# RGB_ADDR_THRU.net
KiCad netlist of a schematic drawn in EAGLE
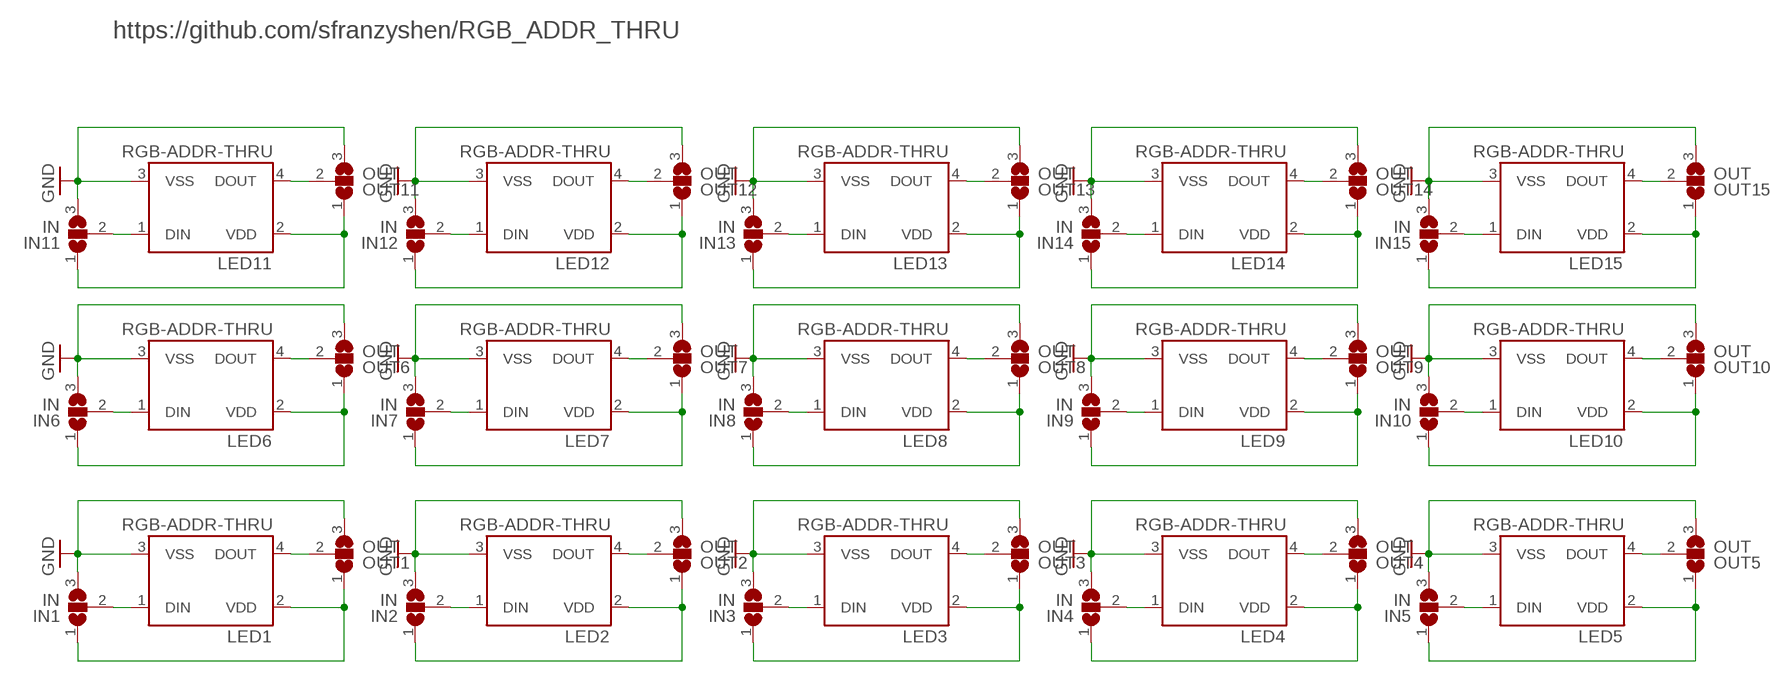
[diagram p0: schematic, sheet 1]

(export (version "E")
  (design (tool "Eeschema 10.0.6"))
  (components
    (comp (ref "IN1")
      (value "IN")
      (footprint "eagle-import:SJ_2W")
      (libsource (lib "eagle-import") (part "SJ2WW"))
    )
    (comp (ref "IN2")
      (value "IN")
      (footprint "eagle-import:SJ_2W")
      (libsource (lib "eagle-import") (part "SJ2WW"))
    )
    (comp (ref "IN3")
      (value "IN")
      (footprint "eagle-import:SJ_2W")
      (libsource (lib "eagle-import") (part "SJ2WW"))
    )
    (comp (ref "IN4")
      (value "IN")
      (footprint "eagle-import:SJ_2W")
      (libsource (lib "eagle-import") (part "SJ2WW"))
    )
    (comp (ref "IN5")
      (value "IN")
      (footprint "eagle-import:SJ_2W")
      (libsource (lib "eagle-import") (part "SJ2WW"))
    )
    (comp (ref "IN6")
      (value "IN")
      (footprint "eagle-import:SJ_2W")
      (libsource (lib "eagle-import") (part "SJ2WW"))
    )
    (comp (ref "IN7")
      (value "IN")
      (footprint "eagle-import:SJ_2W")
      (libsource (lib "eagle-import") (part "SJ2WW"))
    )
    (comp (ref "IN8")
      (value "IN")
      (footprint "eagle-import:SJ_2W")
      (libsource (lib "eagle-import") (part "SJ2WW"))
    )
    (comp (ref "IN9")
      (value "IN")
      (footprint "eagle-import:SJ_2W")
      (libsource (lib "eagle-import") (part "SJ2WW"))
    )
    (comp (ref "IN10")
      (value "IN")
      (footprint "eagle-import:SJ_2W")
      (libsource (lib "eagle-import") (part "SJ2WW"))
    )
    (comp (ref "IN11")
      (value "IN")
      (footprint "eagle-import:SJ_2W")
      (libsource (lib "eagle-import") (part "SJ2WW"))
    )
    (comp (ref "IN12")
      (value "IN")
      (footprint "eagle-import:SJ_2W")
      (libsource (lib "eagle-import") (part "SJ2WW"))
    )
    (comp (ref "IN13")
      (value "IN")
      (footprint "eagle-import:SJ_2W")
      (libsource (lib "eagle-import") (part "SJ2WW"))
    )
    (comp (ref "IN14")
      (value "IN")
      (footprint "eagle-import:SJ_2W")
      (libsource (lib "eagle-import") (part "SJ2WW"))
    )
    (comp (ref "IN15")
      (value "IN")
      (footprint "eagle-import:SJ_2W")
      (libsource (lib "eagle-import") (part "SJ2WW"))
    )
    (comp (ref "LED1")
      (value "RGB-ADDR-THRU")
      (footprint "eagle-import:LED-RGB-THRU")
      (libsource (lib "eagle-import") (part "LED-RGB-ADDR-THRU5MM"))
    )
    (comp (ref "LED2")
      (value "RGB-ADDR-THRU")
      (footprint "eagle-import:LED-RGB-THRU")
      (libsource (lib "eagle-import") (part "LED-RGB-ADDR-THRU5MM"))
    )
    (comp (ref "LED3")
      (value "RGB-ADDR-THRU")
      (footprint "eagle-import:LED-RGB-THRU")
      (libsource (lib "eagle-import") (part "LED-RGB-ADDR-THRU5MM"))
    )
    (comp (ref "LED4")
      (value "RGB-ADDR-THRU")
      (footprint "eagle-import:LED-RGB-THRU")
      (libsource (lib "eagle-import") (part "LED-RGB-ADDR-THRU5MM"))
    )
    (comp (ref "LED5")
      (value "RGB-ADDR-THRU")
      (footprint "eagle-import:LED-RGB-THRU")
      (libsource (lib "eagle-import") (part "LED-RGB-ADDR-THRU5MM"))
    )
    (comp (ref "LED6")
      (value "RGB-ADDR-THRU")
      (footprint "eagle-import:LED-RGB-THRU")
      (libsource (lib "eagle-import") (part "LED-RGB-ADDR-THRU5MM"))
    )
    (comp (ref "LED7")
      (value "RGB-ADDR-THRU")
      (footprint "eagle-import:LED-RGB-THRU")
      (libsource (lib "eagle-import") (part "LED-RGB-ADDR-THRU5MM"))
    )
    (comp (ref "LED8")
      (value "RGB-ADDR-THRU")
      (footprint "eagle-import:LED-RGB-THRU")
      (libsource (lib "eagle-import") (part "LED-RGB-ADDR-THRU5MM"))
    )
    (comp (ref "LED9")
      (value "RGB-ADDR-THRU")
      (footprint "eagle-import:LED-RGB-THRU")
      (libsource (lib "eagle-import") (part "LED-RGB-ADDR-THRU5MM"))
    )
    (comp (ref "LED10")
      (value "RGB-ADDR-THRU")
      (footprint "eagle-import:LED-RGB-THRU")
      (libsource (lib "eagle-import") (part "LED-RGB-ADDR-THRU5MM"))
    )
    (comp (ref "LED11")
      (value "RGB-ADDR-THRU")
      (footprint "eagle-import:LED-RGB-THRU")
      (libsource (lib "eagle-import") (part "LED-RGB-ADDR-THRU5MM"))
    )
    (comp (ref "LED12")
      (value "RGB-ADDR-THRU")
      (footprint "eagle-import:LED-RGB-THRU")
      (libsource (lib "eagle-import") (part "LED-RGB-ADDR-THRU5MM"))
    )
    (comp (ref "LED13")
      (value "RGB-ADDR-THRU")
      (footprint "eagle-import:LED-RGB-THRU")
      (libsource (lib "eagle-import") (part "LED-RGB-ADDR-THRU5MM"))
    )
    (comp (ref "LED14")
      (value "RGB-ADDR-THRU")
      (footprint "eagle-import:LED-RGB-THRU")
      (libsource (lib "eagle-import") (part "LED-RGB-ADDR-THRU5MM"))
    )
    (comp (ref "LED15")
      (value "RGB-ADDR-THRU")
      (footprint "eagle-import:LED-RGB-THRU")
      (libsource (lib "eagle-import") (part "LED-RGB-ADDR-THRU5MM"))
    )
    (comp (ref "OUT1")
      (value "OUT")
      (footprint "eagle-import:SJ_2W")
      (libsource (lib "eagle-import") (part "SJ2WW"))
    )
    (comp (ref "OUT2")
      (value "OUT")
      (footprint "eagle-import:SJ_2W")
      (libsource (lib "eagle-import") (part "SJ2WW"))
    )
    (comp (ref "OUT3")
      (value "OUT")
      (footprint "eagle-import:SJ_2W")
      (libsource (lib "eagle-import") (part "SJ2WW"))
    )
    (comp (ref "OUT4")
      (value "OUT")
      (footprint "eagle-import:SJ_2W")
      (libsource (lib "eagle-import") (part "SJ2WW"))
    )
    (comp (ref "OUT5")
      (value "OUT")
      (footprint "eagle-import:SJ_2W")
      (libsource (lib "eagle-import") (part "SJ2WW"))
    )
    (comp (ref "OUT6")
      (value "OUT")
      (footprint "eagle-import:SJ_2W")
      (libsource (lib "eagle-import") (part "SJ2WW"))
    )
    (comp (ref "OUT7")
      (value "OUT")
      (footprint "eagle-import:SJ_2W")
      (libsource (lib "eagle-import") (part "SJ2WW"))
    )
    (comp (ref "OUT8")
      (value "OUT")
      (footprint "eagle-import:SJ_2W")
      (libsource (lib "eagle-import") (part "SJ2WW"))
    )
    (comp (ref "OUT9")
      (value "OUT")
      (footprint "eagle-import:SJ_2W")
      (libsource (lib "eagle-import") (part "SJ2WW"))
    )
    (comp (ref "OUT10")
      (value "OUT")
      (footprint "eagle-import:SJ_2W")
      (libsource (lib "eagle-import") (part "SJ2WW"))
    )
    (comp (ref "OUT11")
      (value "OUT")
      (footprint "eagle-import:SJ_2W")
      (libsource (lib "eagle-import") (part "SJ2WW"))
    )
    (comp (ref "OUT12")
      (value "OUT")
      (footprint "eagle-import:SJ_2W")
      (libsource (lib "eagle-import") (part "SJ2WW"))
    )
    (comp (ref "OUT13")
      (value "OUT")
      (footprint "eagle-import:SJ_2W")
      (libsource (lib "eagle-import") (part "SJ2WW"))
    )
    (comp (ref "OUT14")
      (value "OUT")
      (footprint "eagle-import:SJ_2W")
      (libsource (lib "eagle-import") (part "SJ2WW"))
    )
    (comp (ref "OUT15")
      (value "OUT")
      (footprint "eagle-import:SJ_2W")
      (libsource (lib "eagle-import") (part "SJ2WW"))
    )
  )
  (nets
    (net (code "1") (name "GND") (class "Default")
      (node (ref "IN1") (pin "3") (pinfunction "3_3") (pintype "passive"))
      (node (ref "IN10") (pin "3") (pinfunction "3_3") (pintype "passive"))
      (node (ref "IN11") (pin "3") (pinfunction "3_3") (pintype "passive"))
      (node (ref "IN12") (pin "3") (pinfunction "3_3") (pintype "passive"))
      (node (ref "IN13") (pin "3") (pinfunction "3_3") (pintype "passive"))
      (node (ref "IN14") (pin "3") (pinfunction "3_3") (pintype "passive"))
      (node (ref "IN15") (pin "3") (pinfunction "3_3") (pintype "passive"))
      (node (ref "IN2") (pin "3") (pinfunction "3_3") (pintype "passive"))
      (node (ref "IN3") (pin "3") (pinfunction "3_3") (pintype "passive"))
      (node (ref "IN4") (pin "3") (pinfunction "3_3") (pintype "passive"))
      (node (ref "IN5") (pin "3") (pinfunction "3_3") (pintype "passive"))
      (node (ref "IN6") (pin "3") (pinfunction "3_3") (pintype "passive"))
      (node (ref "IN7") (pin "3") (pinfunction "3_3") (pintype "passive"))
      (node (ref "IN8") (pin "3") (pinfunction "3_3") (pintype "passive"))
      (node (ref "IN9") (pin "3") (pinfunction "3_3") (pintype "passive"))
      (node (ref "LED1") (pin "3") (pinfunction "VSS_3") (pintype "power_in"))
      (node (ref "LED10") (pin "3") (pinfunction "VSS_3") (pintype "power_in"))
      (node (ref "LED11") (pin "3") (pinfunction "VSS_3") (pintype "power_in"))
      (node (ref "LED12") (pin "3") (pinfunction "VSS_3") (pintype "power_in"))
      (node (ref "LED13") (pin "3") (pinfunction "VSS_3") (pintype "power_in"))
      (node (ref "LED14") (pin "3") (pinfunction "VSS_3") (pintype "power_in"))
      (node (ref "LED15") (pin "3") (pinfunction "VSS_3") (pintype "power_in"))
      (node (ref "LED2") (pin "3") (pinfunction "VSS_3") (pintype "power_in"))
      (node (ref "LED3") (pin "3") (pinfunction "VSS_3") (pintype "power_in"))
      (node (ref "LED4") (pin "3") (pinfunction "VSS_3") (pintype "power_in"))
      (node (ref "LED5") (pin "3") (pinfunction "VSS_3") (pintype "power_in"))
      (node (ref "LED6") (pin "3") (pinfunction "VSS_3") (pintype "power_in"))
      (node (ref "LED7") (pin "3") (pinfunction "VSS_3") (pintype "power_in"))
      (node (ref "LED8") (pin "3") (pinfunction "VSS_3") (pintype "power_in"))
      (node (ref "LED9") (pin "3") (pinfunction "VSS_3") (pintype "power_in"))
      (node (ref "OUT1") (pin "3") (pinfunction "3_3") (pintype "passive"))
      (node (ref "OUT10") (pin "3") (pinfunction "3_3") (pintype "passive"))
      (node (ref "OUT11") (pin "3") (pinfunction "3_3") (pintype "passive"))
      (node (ref "OUT12") (pin "3") (pinfunction "3_3") (pintype "passive"))
      (node (ref "OUT13") (pin "3") (pinfunction "3_3") (pintype "passive"))
      (node (ref "OUT14") (pin "3") (pinfunction "3_3") (pintype "passive"))
      (node (ref "OUT15") (pin "3") (pinfunction "3_3") (pintype "passive"))
      (node (ref "OUT2") (pin "3") (pinfunction "3_3") (pintype "passive"))
      (node (ref "OUT3") (pin "3") (pinfunction "3_3") (pintype "passive"))
      (node (ref "OUT4") (pin "3") (pinfunction "3_3") (pintype "passive"))
      (node (ref "OUT5") (pin "3") (pinfunction "3_3") (pintype "passive"))
      (node (ref "OUT6") (pin "3") (pinfunction "3_3") (pintype "passive"))
      (node (ref "OUT7") (pin "3") (pinfunction "3_3") (pintype "passive"))
      (node (ref "OUT8") (pin "3") (pinfunction "3_3") (pintype "passive"))
      (node (ref "OUT9") (pin "3") (pinfunction "3_3") (pintype "passive"))
    )
    (net (code "2") (name "Net-(LED1-DIN)") (class "Default")
      (node (ref "IN1") (pin "2") (pinfunction "2_2") (pintype "passive"))
      (node (ref "LED1") (pin "1") (pinfunction "DIN_1") (pintype "input"))
    )
    (net (code "3") (name "Net-(LED1-DOUT)") (class "Default")
      (node (ref "LED1") (pin "4") (pinfunction "DOUT_4") (pintype "output"))
      (node (ref "OUT1") (pin "2") (pinfunction "2_2") (pintype "passive"))
    )
    (net (code "4") (name "Net-(LED1-VDD)") (class "Default")
      (node (ref "IN1") (pin "1") (pinfunction "1_1") (pintype "passive"))
      (node (ref "LED1") (pin "2") (pinfunction "VDD_2") (pintype "power_in"))
      (node (ref "OUT1") (pin "1") (pinfunction "1_1") (pintype "passive"))
    )
    (net (code "5") (name "Net-(LED2-DIN)") (class "Default")
      (node (ref "IN2") (pin "2") (pinfunction "2_2") (pintype "passive"))
      (node (ref "LED2") (pin "1") (pinfunction "DIN_1") (pintype "input"))
    )
    (net (code "6") (name "Net-(LED2-DOUT)") (class "Default")
      (node (ref "LED2") (pin "4") (pinfunction "DOUT_4") (pintype "output"))
      (node (ref "OUT2") (pin "2") (pinfunction "2_2") (pintype "passive"))
    )
    (net (code "7") (name "Net-(LED2-VDD)") (class "Default")
      (node (ref "IN2") (pin "1") (pinfunction "1_1") (pintype "passive"))
      (node (ref "LED2") (pin "2") (pinfunction "VDD_2") (pintype "power_in"))
      (node (ref "OUT2") (pin "1") (pinfunction "1_1") (pintype "passive"))
    )
    (net (code "8") (name "Net-(LED3-DIN)") (class "Default")
      (node (ref "IN3") (pin "2") (pinfunction "2_2") (pintype "passive"))
      (node (ref "LED3") (pin "1") (pinfunction "DIN_1") (pintype "input"))
    )
    (net (code "9") (name "Net-(LED3-DOUT)") (class "Default")
      (node (ref "LED3") (pin "4") (pinfunction "DOUT_4") (pintype "output"))
      (node (ref "OUT3") (pin "2") (pinfunction "2_2") (pintype "passive"))
    )
    (net (code "10") (name "Net-(LED3-VDD)") (class "Default")
      (node (ref "IN3") (pin "1") (pinfunction "1_1") (pintype "passive"))
      (node (ref "LED3") (pin "2") (pinfunction "VDD_2") (pintype "power_in"))
      (node (ref "OUT3") (pin "1") (pinfunction "1_1") (pintype "passive"))
    )
    (net (code "11") (name "Net-(LED4-DIN)") (class "Default")
      (node (ref "IN4") (pin "2") (pinfunction "2_2") (pintype "passive"))
      (node (ref "LED4") (pin "1") (pinfunction "DIN_1") (pintype "input"))
    )
    (net (code "12") (name "Net-(LED4-DOUT)") (class "Default")
      (node (ref "LED4") (pin "4") (pinfunction "DOUT_4") (pintype "output"))
      (node (ref "OUT4") (pin "2") (pinfunction "2_2") (pintype "passive"))
    )
    (net (code "13") (name "Net-(LED4-VDD)") (class "Default")
      (node (ref "IN4") (pin "1") (pinfunction "1_1") (pintype "passive"))
      (node (ref "LED4") (pin "2") (pinfunction "VDD_2") (pintype "power_in"))
      (node (ref "OUT4") (pin "1") (pinfunction "1_1") (pintype "passive"))
    )
    (net (code "14") (name "Net-(LED5-DIN)") (class "Default")
      (node (ref "IN5") (pin "2") (pinfunction "2_2") (pintype "passive"))
      (node (ref "LED5") (pin "1") (pinfunction "DIN_1") (pintype "input"))
    )
    (net (code "15") (name "Net-(LED5-DOUT)") (class "Default")
      (node (ref "LED5") (pin "4") (pinfunction "DOUT_4") (pintype "output"))
      (node (ref "OUT5") (pin "2") (pinfunction "2_2") (pintype "passive"))
    )
    (net (code "16") (name "Net-(LED5-VDD)") (class "Default")
      (node (ref "IN5") (pin "1") (pinfunction "1_1") (pintype "passive"))
      (node (ref "LED5") (pin "2") (pinfunction "VDD_2") (pintype "power_in"))
      (node (ref "OUT5") (pin "1") (pinfunction "1_1") (pintype "passive"))
    )
    (net (code "17") (name "Net-(LED6-DIN)") (class "Default")
      (node (ref "IN6") (pin "2") (pinfunction "2_2") (pintype "passive"))
      (node (ref "LED6") (pin "1") (pinfunction "DIN_1") (pintype "input"))
    )
    (net (code "18") (name "Net-(LED6-DOUT)") (class "Default")
      (node (ref "LED6") (pin "4") (pinfunction "DOUT_4") (pintype "output"))
      (node (ref "OUT6") (pin "2") (pinfunction "2_2") (pintype "passive"))
    )
    (net (code "19") (name "Net-(LED6-VDD)") (class "Default")
      (node (ref "IN6") (pin "1") (pinfunction "1_1") (pintype "passive"))
      (node (ref "LED6") (pin "2") (pinfunction "VDD_2") (pintype "power_in"))
      (node (ref "OUT6") (pin "1") (pinfunction "1_1") (pintype "passive"))
    )
    (net (code "20") (name "Net-(LED7-DIN)") (class "Default")
      (node (ref "IN7") (pin "2") (pinfunction "2_2") (pintype "passive"))
      (node (ref "LED7") (pin "1") (pinfunction "DIN_1") (pintype "input"))
    )
    (net (code "21") (name "Net-(LED7-DOUT)") (class "Default")
      (node (ref "LED7") (pin "4") (pinfunction "DOUT_4") (pintype "output"))
      (node (ref "OUT7") (pin "2") (pinfunction "2_2") (pintype "passive"))
    )
    (net (code "22") (name "Net-(LED7-VDD)") (class "Default")
      (node (ref "IN7") (pin "1") (pinfunction "1_1") (pintype "passive"))
      (node (ref "LED7") (pin "2") (pinfunction "VDD_2") (pintype "power_in"))
      (node (ref "OUT7") (pin "1") (pinfunction "1_1") (pintype "passive"))
    )
    (net (code "23") (name "Net-(LED8-DIN)") (class "Default")
      (node (ref "IN8") (pin "2") (pinfunction "2_2") (pintype "passive"))
      (node (ref "LED8") (pin "1") (pinfunction "DIN_1") (pintype "input"))
    )
    (net (code "24") (name "Net-(LED8-DOUT)") (class "Default")
      (node (ref "LED8") (pin "4") (pinfunction "DOUT_4") (pintype "output"))
      (node (ref "OUT8") (pin "2") (pinfunction "2_2") (pintype "passive"))
    )
    (net (code "25") (name "Net-(LED8-VDD)") (class "Default")
      (node (ref "IN8") (pin "1") (pinfunction "1_1") (pintype "passive"))
      (node (ref "LED8") (pin "2") (pinfunction "VDD_2") (pintype "power_in"))
      (node (ref "OUT8") (pin "1") (pinfunction "1_1") (pintype "passive"))
    )
    (net (code "26") (name "Net-(LED9-DIN)") (class "Default")
      (node (ref "IN9") (pin "2") (pinfunction "2_2") (pintype "passive"))
      (node (ref "LED9") (pin "1") (pinfunction "DIN_1") (pintype "input"))
    )
    (net (code "27") (name "Net-(LED9-DOUT)") (class "Default")
      (node (ref "LED9") (pin "4") (pinfunction "DOUT_4") (pintype "output"))
      (node (ref "OUT9") (pin "2") (pinfunction "2_2") (pintype "passive"))
    )
    (net (code "28") (name "Net-(LED9-VDD)") (class "Default")
      (node (ref "IN9") (pin "1") (pinfunction "1_1") (pintype "passive"))
      (node (ref "LED9") (pin "2") (pinfunction "VDD_2") (pintype "power_in"))
      (node (ref "OUT9") (pin "1") (pinfunction "1_1") (pintype "passive"))
    )
    (net (code "29") (name "Net-(LED10-DIN)") (class "Default")
      (node (ref "IN10") (pin "2") (pinfunction "2_2") (pintype "passive"))
      (node (ref "LED10") (pin "1") (pinfunction "DIN_1") (pintype "input"))
    )
    (net (code "30") (name "Net-(LED10-DOUT)") (class "Default")
      (node (ref "LED10") (pin "4") (pinfunction "DOUT_4") (pintype "output"))
      (node (ref "OUT10") (pin "2") (pinfunction "2_2") (pintype "passive"))
    )
    (net (code "31") (name "Net-(LED10-VDD)") (class "Default")
      (node (ref "IN10") (pin "1") (pinfunction "1_1") (pintype "passive"))
      (node (ref "LED10") (pin "2") (pinfunction "VDD_2") (pintype "power_in"))
      (node (ref "OUT10") (pin "1") (pinfunction "1_1") (pintype "passive"))
    )
    (net (code "32") (name "Net-(LED11-DIN)") (class "Default")
      (node (ref "IN11") (pin "2") (pinfunction "2_2") (pintype "passive"))
      (node (ref "LED11") (pin "1") (pinfunction "DIN_1") (pintype "input"))
    )
    (net (code "33") (name "Net-(LED11-DOUT)") (class "Default")
      (node (ref "LED11") (pin "4") (pinfunction "DOUT_4") (pintype "output"))
      (node (ref "OUT11") (pin "2") (pinfunction "2_2") (pintype "passive"))
    )
    (net (code "34") (name "Net-(LED11-VDD)") (class "Default")
      (node (ref "IN11") (pin "1") (pinfunction "1_1") (pintype "passive"))
      (node (ref "LED11") (pin "2") (pinfunction "VDD_2") (pintype "power_in"))
      (node (ref "OUT11") (pin "1") (pinfunction "1_1") (pintype "passive"))
    )
    (net (code "35") (name "Net-(LED12-DIN)") (class "Default")
      (node (ref "IN12") (pin "2") (pinfunction "2_2") (pintype "passive"))
      (node (ref "LED12") (pin "1") (pinfunction "DIN_1") (pintype "input"))
    )
    (net (code "36") (name "Net-(LED12-DOUT)") (class "Default")
      (node (ref "LED12") (pin "4") (pinfunction "DOUT_4") (pintype "output"))
      (node (ref "OUT12") (pin "2") (pinfunction "2_2") (pintype "passive"))
    )
    (net (code "37") (name "Net-(LED12-VDD)") (class "Default")
      (node (ref "IN12") (pin "1") (pinfunction "1_1") (pintype "passive"))
      (node (ref "LED12") (pin "2") (pinfunction "VDD_2") (pintype "power_in"))
      (node (ref "OUT12") (pin "1") (pinfunction "1_1") (pintype "passive"))
    )
    (net (code "38") (name "Net-(LED13-DIN)") (class "Default")
      (node (ref "IN13") (pin "2") (pinfunction "2_2") (pintype "passive"))
      (node (ref "LED13") (pin "1") (pinfunction "DIN_1") (pintype "input"))
    )
    (net (code "39") (name "Net-(LED13-DOUT)") (class "Default")
      (node (ref "LED13") (pin "4") (pinfunction "DOUT_4") (pintype "output"))
      (node (ref "OUT13") (pin "2") (pinfunction "2_2") (pintype "passive"))
    )
    (net (code "40") (name "Net-(LED13-VDD)") (class "Default")
      (node (ref "IN13") (pin "1") (pinfunction "1_1") (pintype "passive"))
      (node (ref "LED13") (pin "2") (pinfunction "VDD_2") (pintype "power_in"))
      (node (ref "OUT13") (pin "1") (pinfunction "1_1") (pintype "passive"))
    )
    (net (code "41") (name "Net-(LED14-DIN)") (class "Default")
      (node (ref "IN14") (pin "2") (pinfunction "2_2") (pintype "passive"))
      (node (ref "LED14") (pin "1") (pinfunction "DIN_1") (pintype "input"))
    )
    (net (code "42") (name "Net-(LED14-DOUT)") (class "Default")
      (node (ref "LED14") (pin "4") (pinfunction "DOUT_4") (pintype "output"))
      (node (ref "OUT14") (pin "2") (pinfunction "2_2") (pintype "passive"))
    )
    (net (code "43") (name "Net-(LED14-VDD)") (class "Default")
      (node (ref "IN14") (pin "1") (pinfunction "1_1") (pintype "passive"))
      (node (ref "LED14") (pin "2") (pinfunction "VDD_2") (pintype "power_in"))
      (node (ref "OUT14") (pin "1") (pinfunction "1_1") (pintype "passive"))
    )
    (net (code "44") (name "Net-(LED15-DIN)") (class "Default")
      (node (ref "IN15") (pin "2") (pinfunction "2_2") (pintype "passive"))
      (node (ref "LED15") (pin "1") (pinfunction "DIN_1") (pintype "input"))
    )
    (net (code "45") (name "Net-(LED15-DOUT)") (class "Default")
      (node (ref "LED15") (pin "4") (pinfunction "DOUT_4") (pintype "output"))
      (node (ref "OUT15") (pin "2") (pinfunction "2_2") (pintype "passive"))
    )
    (net (code "46") (name "Net-(LED15-VDD)") (class "Default")
      (node (ref "IN15") (pin "1") (pinfunction "1_1") (pintype "passive"))
      (node (ref "LED15") (pin "2") (pinfunction "VDD_2") (pintype "power_in"))
      (node (ref "OUT15") (pin "1") (pinfunction "1_1") (pintype "passive"))
    )
  )
)
